# POWER.net
KiCad netlist of a schematic drawn in Altium Designer
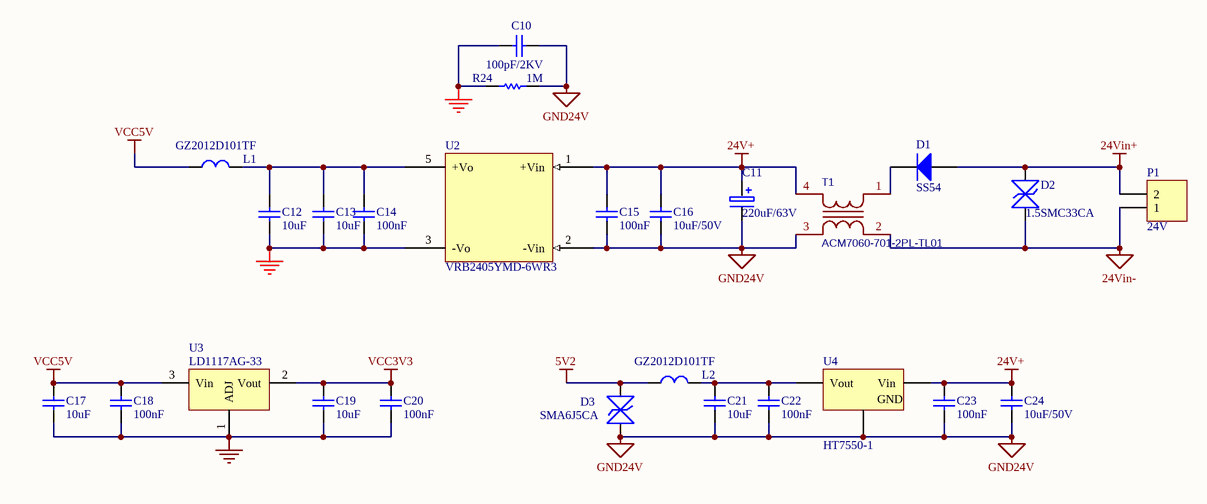
[diagram p0: POWER.SchDoc]

(export (version "E")
  (design (tool "Eeschema 10.0.6"))
  (components
    (comp (ref "C10")
      (value "100pF/2KV")
      (footprint "1206_C")
      (description "Capacitor")
      (fields (field (name "PUBLISHER") "Altium Limited"))
      (libsource (lib "Miscellaneous Devices") (part "Cap"))
    )
    (comp (ref "C11")
      (value "220uF/63V")
      (footprint "CAP-TH_BD10.0-P5.00-D1.0-FD")
      (description "Electrolytic Capacitor")
      (libsource (lib "*") (part "CD1"))
    )
    (comp (ref "C12")
      (value "10uF")
      (footprint "0805_C")
      (description "贴片电容")
      (libsource (lib "Miscellaneous Devices LC") (part "0805 10uF (106) 10% 25V"))
    )
    (comp (ref "C13")
      (value "10uF")
      (footprint "0805_C")
      (description "贴片电容")
      (libsource (lib "Miscellaneous Devices LC") (part "0805 10uF (106) 10% 25V"))
    )
    (comp (ref "C14")
      (value "100nF")
      (footprint "0805_C")
      (description "贴片电容")
      (libsource (lib "Miscellaneous Devices LC") (part "0805 100nF(104) 10% 50V"))
    )
    (comp (ref "C15")
      (value "100nF")
      (footprint "0805_C")
      (description "贴片电容")
      (libsource (lib "Miscellaneous Devices LC") (part "0805 100nF(104) 10% 50V"))
    )
    (comp (ref "C16")
      (value "10uF/50V")
      (footprint "1206_C")
      (description "贴片电容")
      (libsource (lib "Miscellaneous Devices LC") (part "1206 10uF (106) 10% 50V"))
    )
    (comp (ref "C17")
      (value "10uF")
      (footprint "0805_C")
      (description "贴片电容")
      (libsource (lib "Miscellaneous Devices LC") (part "0805 10uF (106) 10% 25V"))
    )
    (comp (ref "C18")
      (value "100nF")
      (footprint "0805_C")
      (description "贴片电容")
      (libsource (lib "Miscellaneous Devices LC") (part "0805 100nF(104) 10% 50V"))
    )
    (comp (ref "C19")
      (value "10uF")
      (footprint "0805_C")
      (description "贴片电容")
      (libsource (lib "Miscellaneous Devices LC") (part "0805 10uF (106) 10% 25V"))
    )
    (comp (ref "C20")
      (value "100nF")
      (footprint "0805_C")
      (description "贴片电容")
      (libsource (lib "Miscellaneous Devices LC") (part "0805 100nF(104) 10% 50V"))
    )
    (comp (ref "C21")
      (value "10uF")
      (footprint "0805_C")
      (description "贴片电容")
      (libsource (lib "Miscellaneous Devices LC") (part "0805 10uF (106) 10% 25V"))
    )
    (comp (ref "C22")
      (value "100nF")
      (footprint "0805_C")
      (description "贴片电容")
      (libsource (lib "Miscellaneous Devices LC") (part "0805 100nF(104) 10% 50V"))
    )
    (comp (ref "C23")
      (value "100nF")
      (footprint "0805_C")
      (description "贴片电容")
      (libsource (lib "Miscellaneous Devices LC") (part "0805 100nF(104) 10% 50V"))
    )
    (comp (ref "C24")
      (value "10uF/50V")
      (footprint "1206_C")
      (description "贴片电容")
      (libsource (lib "Miscellaneous Devices LC") (part "1206 10uF (106) 10% 50V"))
    )
    (comp (ref "D1")
      (value "SS54")
      (footprint "SMA(DO-214AC)_S1")
      (description "二极管")
      (libsource (lib "Miscellaneous Devices LC") (part "SMA(DO-214AC) SS54"))
    )
    (comp (ref "D2")
      (value "1.5SMC33CA")
      (footprint "Miscellaneous Devices LC:SMC(DO-214AB)_S1")
      (libsource (lib "IC") (part "TVS"))
    )
    (comp (ref "D3") (value "SMA6J5CA") (footprint "SMA") (libsource (lib "IC") (part "TVS")))
    (comp (ref "L1") (value "GZ2012D101TF") (footprint "0805_L") (libsource (lib "Devices") (part "L1")))
    (comp (ref "L2") (value "GZ2012D101TF") (footprint "0805_L") (libsource (lib "Devices") (part "L1")))
    (comp (ref "P1")
      (value "24V")
      (footprint "mc1.5/2-st-3.81")
      (description "Header, 2-Pin")
      (fields (field (name "PUBLISHER") "Altium Limited"))
      (libsource (lib "Miscellaneous Connectors") (part "Header 2"))
    )
    (comp (ref "R24")
      (value "1M")
      (footprint "1206_R")
      (description "Resistor")
      (fields (field (name "PUBLISHER") "Altium Limited"))
      (libsource (lib "Miscellaneous Devices") (part "Res1"))
    )
    (comp (ref "T1")
      (value "ACM7060-701-2PL-TL01")
      (footprint "FILTER-SMD_4P-L7.0-W6.0-BL")
      (fields (field (name "BOM_SUPPLIER PART") "C78246"))
      (libsource (lib "altium-import") (part "root_0_mirrored_ACM7060-701-2PL-TL01_"))
    )
    (comp (ref "U2") (value "VRB2405YMD-6WR3") (footprint "DC/DC-1X1") (libsource (lib "*") (part "48S5")))
    (comp (ref "U3")
      (value "LD1117AG-33")
      (footprint "SOT-223")
      (description "3-Terminal Adjustable Positive Voltage Regulator")
      (libsource (lib "稳压器件") (part "LM1117"))
    )
    (comp (ref "U4")
      (value "HT7550-1")
      (footprint "SOT-89(SOT-89-3)")
      (description "低压差线性稳压(LDO)")
      (libsource (lib "Miscellaneous Devices LC") (part "SOT-89 HT7550-1"))
    )
  )
  (nets
    (net (code "1") (name "5V2") (class "Default")
      (node (ref "D3") (pin "1") (pinfunction "1_1") (pintype "passive"))
      (node (ref "L2") (pin "2") (pinfunction "2_2") (pintype "passive"))
    )
    (net (code "2") (name "24V+") (class "Default")
      (node (ref "C11") (pin "1") (pinfunction "1_1") (pintype "passive"))
      (node (ref "C15") (pin "2") (pinfunction "2_2") (pintype "passive"))
      (node (ref "C16") (pin "2") (pinfunction "2_2") (pintype "passive"))
      (node (ref "C23") (pin "2") (pinfunction "2_2") (pintype "passive"))
      (node (ref "C24") (pin "2") (pinfunction "2_2") (pintype "passive"))
      (node (ref "T1") (pin "4") (pinfunction "4_4") (pintype "passive"))
      (node (ref "U2") (pin "1") (pinfunction "+Vin_1") (pintype "input"))
      (node (ref "U4") (pin "2") (pinfunction "Vin_2") (pintype "passive"))
    )
    (net (code "3") (name "24Vin+") (class "Default")
      (node (ref "D1") (pin "1") (pinfunction "A_1") (pintype "passive"))
      (node (ref "D2") (pin "2") (pinfunction "2_2") (pintype "passive"))
      (node (ref "P1") (pin "2") (pinfunction "2_2") (pintype "passive"))
    )
    (net (code "4") (name "24Vin-") (class "Default")
      (node (ref "D2") (pin "1") (pinfunction "1_1") (pintype "passive"))
      (node (ref "P1") (pin "1") (pinfunction "1_1") (pintype "passive"))
      (node (ref "T1") (pin "2") (pinfunction "2_2") (pintype "passive"))
    )
    (net (code "5") (name "GND") (class "Default")
      (node (ref "C10") (pin "1") (pinfunction "1_1") (pintype "passive"))
      (node (ref "C12") (pin "1") (pinfunction "1_1") (pintype "passive"))
      (node (ref "C13") (pin "1") (pinfunction "1_1") (pintype "passive"))
      (node (ref "C14") (pin "1") (pinfunction "1_1") (pintype "passive"))
      (node (ref "C17") (pin "1") (pinfunction "1_1") (pintype "passive"))
      (node (ref "C18") (pin "1") (pinfunction "1_1") (pintype "passive"))
      (node (ref "C19") (pin "1") (pinfunction "1_1") (pintype "passive"))
      (node (ref "C20") (pin "1") (pinfunction "1_1") (pintype "passive"))
      (node (ref "R24") (pin "1") (pinfunction "1_1") (pintype "passive"))
      (node (ref "U2") (pin "3") (pinfunction "-Vo_3") (pintype "power_in"))
      (node (ref "U3") (pin "1") (pinfunction "ADJ_1") (pintype "passive"))
    )
    (net (code "6") (name "GND24V") (class "Default")
      (node (ref "C10") (pin "2") (pinfunction "2_2") (pintype "passive"))
      (node (ref "C11") (pin "2") (pinfunction "2_2") (pintype "passive"))
      (node (ref "C15") (pin "1") (pinfunction "1_1") (pintype "passive"))
      (node (ref "C16") (pin "1") (pinfunction "1_1") (pintype "passive"))
      (node (ref "C21") (pin "1") (pinfunction "1_1") (pintype "passive"))
      (node (ref "C22") (pin "1") (pinfunction "1_1") (pintype "passive"))
      (node (ref "C23") (pin "1") (pinfunction "1_1") (pintype "passive"))
      (node (ref "C24") (pin "1") (pinfunction "1_1") (pintype "passive"))
      (node (ref "D3") (pin "2") (pinfunction "2_2") (pintype "passive"))
      (node (ref "R24") (pin "2") (pinfunction "2_2") (pintype "passive"))
      (node (ref "T1") (pin "3") (pinfunction "3_3") (pintype "passive"))
      (node (ref "U2") (pin "2") (pinfunction "-Vin_2") (pintype "input"))
      (node (ref "U4") (pin "1") (pinfunction "GND_1") (pintype "passive"))
    )
    (net (code "7") (name "NC") (class "Default")
      (node (ref "U2") (pin "4") (pinfunction "NC_4") (pintype "tri_state"))
    )
    (net (code "8") (name "Net-(D1-K)") (class "Default")
      (node (ref "D1") (pin "2") (pinfunction "K_2") (pintype "passive"))
      (node (ref "T1") (pin "1") (pinfunction "1_1") (pintype "passive"))
    )
    (net (code "9") (name "Net-(U2-+Vo)") (class "Default")
      (node (ref "C12") (pin "2") (pinfunction "2_2") (pintype "passive"))
      (node (ref "C13") (pin "2") (pinfunction "2_2") (pintype "passive"))
      (node (ref "C14") (pin "2") (pinfunction "2_2") (pintype "passive"))
      (node (ref "L1") (pin "1") (pinfunction "1_1") (pintype "passive"))
      (node (ref "U2") (pin "5") (pinfunction "+Vo_5") (pintype "power_in"))
    )
    (net (code "10") (name "Net-(U4-Vout)") (class "Default")
      (node (ref "C21") (pin "2") (pinfunction "2_2") (pintype "passive"))
      (node (ref "C22") (pin "2") (pinfunction "2_2") (pintype "passive"))
      (node (ref "L2") (pin "1") (pinfunction "1_1") (pintype "passive"))
      (node (ref "U4") (pin "3") (pinfunction "Vout_3") (pintype "passive"))
    )
    (net (code "11") (name "VCC3V3") (class "Default")
      (node (ref "C19") (pin "2") (pinfunction "2_2") (pintype "passive"))
      (node (ref "C20") (pin "2") (pinfunction "2_2") (pintype "passive"))
      (node (ref "U3") (pin "2") (pinfunction "Vout_2") (pintype "passive"))
    )
    (net (code "12") (name "VCC5V") (class "Default")
      (node (ref "C17") (pin "2") (pinfunction "2_2") (pintype "passive"))
      (node (ref "C18") (pin "2") (pinfunction "2_2") (pintype "passive"))
      (node (ref "L1") (pin "2") (pinfunction "2_2") (pintype "passive"))
      (node (ref "U3") (pin "3") (pinfunction "Vin_3") (pintype "passive"))
    )
  )
)
